# Connectors.net
KiCad netlist of a schematic drawn in Altium Designer
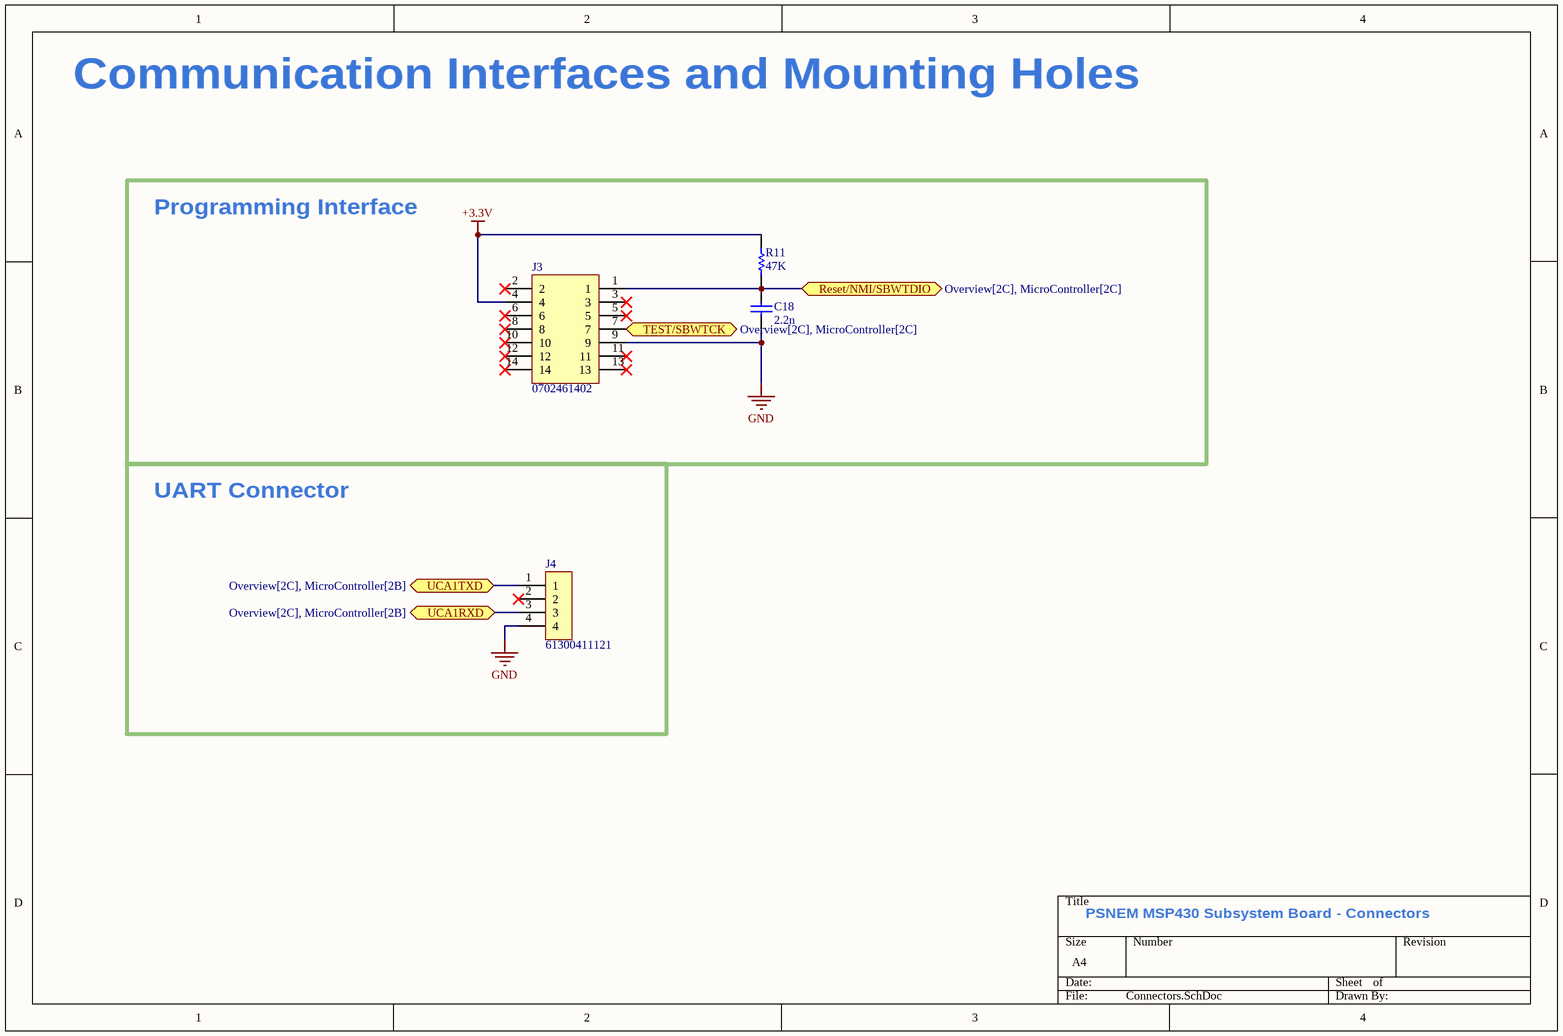
[diagram p0: Connectors.SchDoc]

(export (version "E")
  (design (tool "Eeschema 10.0.6"))
  (components
    (comp (ref "C18")
      (value "2.2n")
      (footprint "0805 Cap")
      (description "2200 pF ±10% 50V Ceramic Capacitor X7R 0805 (2012 Metric)")
      (libsource (lib "Schlib1") (part "CC0805KRX7R9BB222"))
    )
    (comp (ref "J3")
      (value "0702461402")
      (footprint "0702461402")
      (description "Connector Header Through Hole 14 position 0.100\" (2.54mm)")
      (libsource (lib "Schlib1") (part "0702461402"))
    )
    (comp (ref "J4")
      (value "61300411121")
      (footprint "61300411121")
      (description "Connector Header Through Hole 4 position 0.100\" (2.54mm)")
      (libsource (lib "Schlib1") (part "61300411121"))
    )
    (comp (ref "R11")
      (value "47K")
      (footprint "RESC1608X06N")
      (description "Thin Film Resistors - SMD 0603 0.1% 47Kohm 25ppm SMD")
      (libsource (lib "Schlib1") (part "ERA-3VEB4702V"))
    )
  )
  (nets
    (net (code "1") (name "+3.3V") (class "Default")
      (node (ref "J3") (pin "4") (pinfunction "4_4") (pintype "passive"))
      (node (ref "R11") (pin "2") (pinfunction "2_2") (pintype "passive"))
    )
    (net (code "2") (name "/Reset{slash}NMI{slash}SBWTDIO") (class "Default")
      (node (ref "C18") (pin "2") (pinfunction "2_2") (pintype "passive"))
      (node (ref "J3") (pin "1") (pinfunction "1_1") (pintype "passive"))
      (node (ref "R11") (pin "1") (pinfunction "1_1") (pintype "passive"))
    )
    (net (code "3") (name "/TEST{slash}SBWTCK") (class "Default")
      (node (ref "J3") (pin "7") (pinfunction "7_7") (pintype "passive"))
    )
    (net (code "4") (name "/UCA1RXD") (class "Default")
      (node (ref "J4") (pin "3") (pinfunction "3_3") (pintype "passive"))
    )
    (net (code "5") (name "/UCA1TXD") (class "Default")
      (node (ref "J4") (pin "1") (pinfunction "1_1") (pintype "passive"))
    )
    (net (code "6") (name "GND") (class "Default")
      (node (ref "C18") (pin "1") (pinfunction "1_1") (pintype "passive"))
      (node (ref "J3") (pin "9") (pinfunction "9_9") (pintype "passive"))
      (node (ref "J4") (pin "4") (pinfunction "4_4") (pintype "passive"))
    )
    (net (code "7") (name "unconnected-(J3-Pad2)") (class "Default")
      (node (ref "J3") (pin "2") (pinfunction "2_2") (pintype "passive+no_connect"))
    )
    (net (code "8") (name "unconnected-(J3-Pad3)") (class "Default")
      (node (ref "J3") (pin "3") (pinfunction "3_3") (pintype "passive+no_connect"))
    )
    (net (code "9") (name "unconnected-(J3-Pad5)") (class "Default")
      (node (ref "J3") (pin "5") (pinfunction "5_5") (pintype "passive+no_connect"))
    )
    (net (code "10") (name "unconnected-(J3-Pad6)") (class "Default")
      (node (ref "J3") (pin "6") (pinfunction "6_6") (pintype "passive+no_connect"))
    )
    (net (code "11") (name "unconnected-(J3-Pad8)") (class "Default")
      (node (ref "J3") (pin "8") (pinfunction "8_8") (pintype "passive+no_connect"))
    )
    (net (code "12") (name "unconnected-(J3-Pad10)") (class "Default")
      (node (ref "J3") (pin "10") (pinfunction "10_10") (pintype "passive+no_connect"))
    )
    (net (code "13") (name "unconnected-(J3-Pad11)") (class "Default")
      (node (ref "J3") (pin "11") (pinfunction "11_11") (pintype "passive+no_connect"))
    )
    (net (code "14") (name "unconnected-(J3-Pad12)") (class "Default")
      (node (ref "J3") (pin "12") (pinfunction "12_12") (pintype "passive+no_connect"))
    )
    (net (code "15") (name "unconnected-(J3-Pad13)") (class "Default")
      (node (ref "J3") (pin "13") (pinfunction "13_13") (pintype "passive+no_connect"))
    )
    (net (code "16") (name "unconnected-(J3-Pad14)") (class "Default")
      (node (ref "J3") (pin "14") (pinfunction "14_14") (pintype "passive+no_connect"))
    )
    (net (code "17") (name "unconnected-(J4-Pad2)") (class "Default")
      (node (ref "J4") (pin "2") (pinfunction "2_2") (pintype "passive+no_connect"))
    )
  )
)
